# PR9023.net
KiCad netlist of a schematic drawn in EAGLE
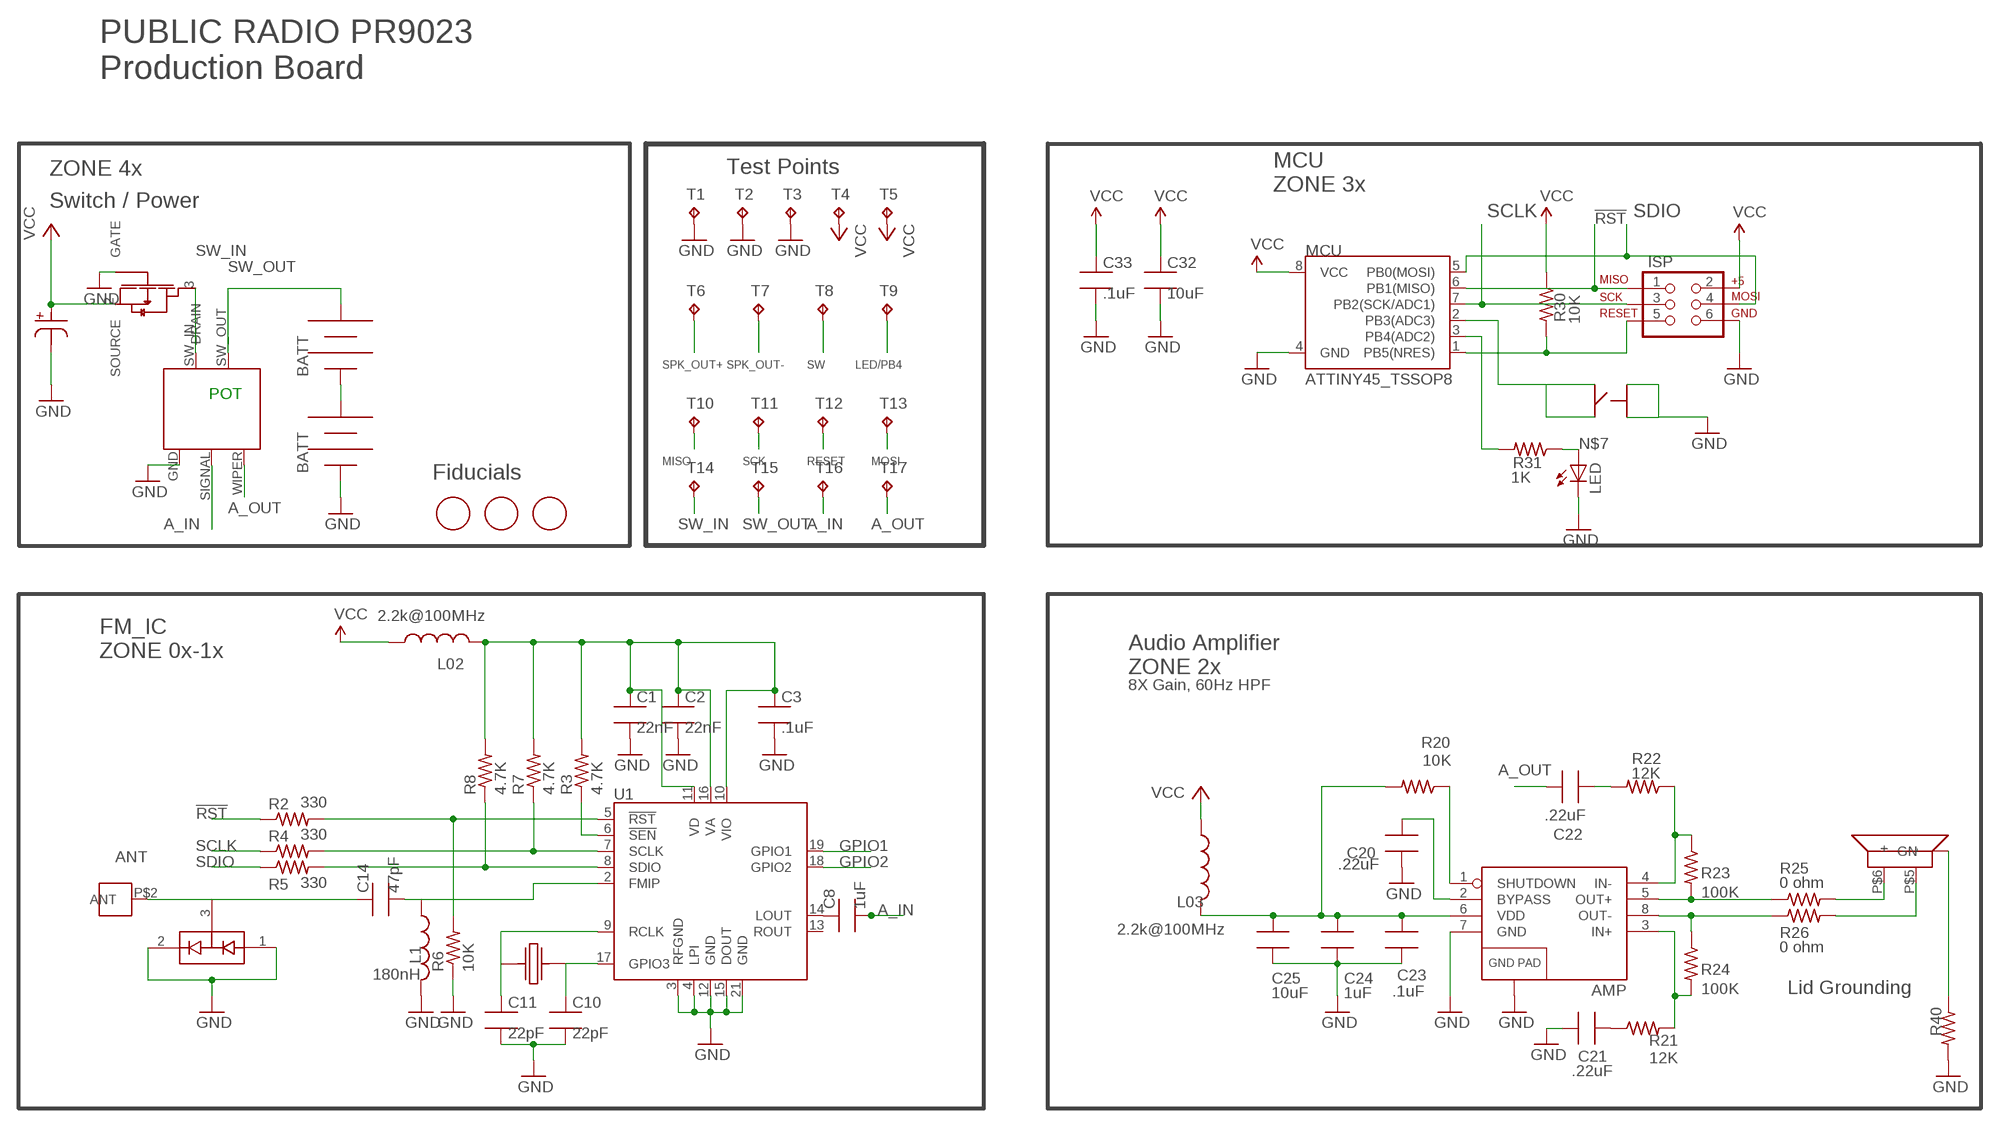
[diagram p0: schematic, sheet 1]

(export (version "E")
  (design (tool "Eeschema 10.0.6"))
  (components
    (comp (ref "AMP")
      (value "TPA6203A1")
      (footprint "eagle-import:8-MSOP")
      (libsource (lib "eagle-import") (part "TPA6203A1"))
    )
    (comp (ref "ANT_MOUNT")
      (value "DNP")
      (footprint "eagle-import:PEM_M3")
      (libsource (lib "eagle-import") (part "M3_PEMNUT"))
    )
    (comp (ref "C1")
      (value "22nF")
      (footprint "eagle-import:0603_CPL")
      (fields
        (field (name "MFG_PN") "CL10B223KB8NNNC")
        (field (name "TOL") "10%")
        (field (name "VOLTAGE") "16V")
      )
      (libsource (lib "eagle-import") (part "C_SMT_0603_CPL"))
    )
    (comp (ref "C2")
      (value "22nF")
      (footprint "eagle-import:0603_CPL")
      (fields
        (field (name "MFG_PN") "CL10B223KB8NNNC")
        (field (name "TOL") "10%")
        (field (name "VOLTAGE") "16V")
      )
      (libsource (lib "eagle-import") (part "C_SMT_0603_CPL"))
    )
    (comp (ref "C3")
      (value ".1uF")
      (footprint "eagle-import:0603_CPL")
      (fields
        (field (name "MFG_PN") "CL10B104KB8SFNC")
        (field (name "TOL") "10%")
        (field (name "VOLTAGE") "16V")
      )
      (libsource (lib "eagle-import") (part "C_SMT_0603_CPL"))
    )
    (comp (ref "C8")
      (value "1uF")
      (footprint "eagle-import:0603_CPL")
      (fields
        (field (name "MFG_PN") "CL10B105KP8NNNC")
        (field (name "TOL") "10%")
        (field (name "VOLTAGE") "10V")
      )
      (libsource (lib "eagle-import") (part "C_SMT_0603_CPL"))
    )
    (comp (ref "C10")
      (value "22pF")
      (footprint "eagle-import:0603_CPL")
      (fields
        (field (name "MFG_PN") "C1608C0G1H220J080AA")
        (field (name "TOL") "5%")
        (field (name "VOLTAGE") "50V")
      )
      (libsource (lib "eagle-import") (part "C_SMT_0603_CPL"))
    )
    (comp (ref "C11")
      (value "22pF")
      (footprint "eagle-import:0603_CPL")
      (fields
        (field (name "MFG_PN") "C1608C0G1H220J080AA")
        (field (name "TOL") "5%")
        (field (name "VOLTAGE") "50V")
      )
      (libsource (lib "eagle-import") (part "C_SMT_0603_CPL"))
    )
    (comp (ref "C14")
      (value "47pF")
      (footprint "eagle-import:0603_CPL")
      (fields
        (field (name "MFG_PN") "CL10C470JB8NCNC")
        (field (name "TOL") "5%")
        (field (name "VOLTAGE") "50V")
      )
      (libsource (lib "eagle-import") (part "C_SMT_0603_CPL"))
    )
    (comp (ref "C20")
      (value ".22uF")
      (footprint "eagle-import:0603_CPL")
      (fields
        (field (name "MFG_PN") "C1608X7R1C224K080AC")
        (field (name "TOL") "10%")
        (field (name "VOLTAGE") "16V")
      )
      (libsource (lib "eagle-import") (part "C_SMT_0603_CPL"))
    )
    (comp (ref "C21")
      (value ".22uF")
      (footprint "eagle-import:0603_CPL")
      (fields
        (field (name "MFG_PN") "C1608X7R1C224K080AC")
        (field (name "TOL") "10%")
        (field (name "VOLTAGE") "16V")
      )
      (libsource (lib "eagle-import") (part "C_SMT_0603_CPL"))
    )
    (comp (ref "C22")
      (value ".22uF")
      (footprint "eagle-import:0603_CPL")
      (fields
        (field (name "MFG_PN") "C1608X7R1C224K080AC")
        (field (name "TOL") "10%")
        (field (name "VOLTAGE") "16V")
      )
      (libsource (lib "eagle-import") (part "C_SMT_0603_CPL"))
    )
    (comp (ref "C23")
      (value ".1uF")
      (footprint "eagle-import:0603_CPL")
      (fields
        (field (name "MFG_PN") "CL10B104KB8SFNC")
        (field (name "TOL") "10%")
        (field (name "VOLTAGE") "16V")
      )
      (libsource (lib "eagle-import") (part "C_SMT_0603_CPL"))
    )
    (comp (ref "C24")
      (value "1uF")
      (footprint "eagle-import:0603_CPL")
      (fields
        (field (name "MFG_PN") "CL10B105KP8NNNC")
        (field (name "TOL") "10%")
        (field (name "VOLTAGE") "10V")
      )
      (libsource (lib "eagle-import") (part "C_SMT_0603_CPL"))
    )
    (comp (ref "C25")
      (value "10uF")
      (footprint "eagle-import:0603_CPL")
      (fields
        (field (name "MFG_PN") "CL10A106MQ8NNNC")
        (field (name "TOL") "20%")
        (field (name "VOLTAGE") "6.3V")
      )
      (libsource (lib "eagle-import") (part "C_SMT_0603_CPL"))
    )
    (comp (ref "C32")
      (value "10uF")
      (footprint "eagle-import:0603_CPL")
      (fields
        (field (name "MFG_PN") "CL10A106MQ8NNNC")
        (field (name "TOL") "20%")
        (field (name "VOLTAGE") "6.3V")
      )
      (libsource (lib "eagle-import") (part "C_SMT_0603_CPL"))
    )
    (comp (ref "C33")
      (value ".1uF")
      (footprint "eagle-import:0603_CPL")
      (fields
        (field (name "MFG_PN") "CL10B104KB8SFNC")
        (field (name "TOL") "10%")
        (field (name "VOLTAGE") "16V")
      )
      (libsource (lib "eagle-import") (part "C_SMT_0603_CPL"))
    )
    (comp (ref "C40")
      (value "220uF")
      (footprint "eagle-import:NICHICON_UD_63")
      (fields (field (name "TOL") "20%") (field (name "VOLTAGE") "16V"))
      (libsource (lib "eagle-import") (part "NICHICON_SERIESUD"))
    )
    (comp (ref "D1")
      (value "BAV99")
      (footprint "eagle-import:SOT23_CPL")
      (fields (field (name "MFG_PN") "BAV99,215"))
      (libsource (lib "eagle-import") (part "BAV99"))
    )
    (comp (ref "FET1")
      (value "AO3435")
      (footprint "eagle-import:SOT23_CPL")
      (fields (field (name "MFG_PN") "AO3435"))
      (libsource (lib "eagle-import") (part "AO3435"))
    )
    (comp (ref "ISP")
      (value "AVR_SPI_PRG_6NS")
      (footprint "eagle-import:2X3-NS")
      (libsource (lib "eagle-import") (part "AVR_SPI_PRG_6NS"))
    )
    (comp (ref "JP5")
      (value "BK-92_MPD_AA_BATT_CLIP")
      (footprint "eagle-import:BK92_AA_BATT")
      (fields (field (name "MFG_PN") "2 of BK92 - supplied by CL Labs"))
      (libsource (lib "eagle-import") (part "BK-92_MPD_AA_BATT_CLIP"))
    )
    (comp (ref "JP6")
      (value "BK-92_MPD_AA_BATT_CLIP")
      (footprint "eagle-import:BK92_AA_BATT")
      (fields (field (name "MFG_PN") "2 of BK92 - supplied by CL Labs"))
      (libsource (lib "eagle-import") (part "BK-92_MPD_AA_BATT_CLIP"))
    )
    (comp (ref "L1")
      (value "180nH")
      (footprint "eagle-import:0805_ADAFRUIT")
      (fields
        (field (name "CURRENT") "400mA")
        (field (name "DCR") "640m")
        (field (name "MFG_PN") "AISC-0805-R18J-T")
        (field (name "TOL") "5%")
      )
      (libsource (lib "eagle-import") (part "L_SMT_0805_ADAFRUIT"))
    )
    (comp (ref "L02")
      (value "2.2k@100MHz")
      (footprint "eagle-import:0603_CPL")
      (fields
        (field (name "CURRENT") "150mA")
        (field (name "DCR") "2.3")
        (field (name "MFG_PN") "HZ0603A222R-10")
      )
      (libsource (lib "eagle-import") (part "L_SMT_0603_CPL"))
    )
    (comp (ref "L03")
      (value "2.2k@100MHz")
      (footprint "eagle-import:0603_CPL")
      (fields
        (field (name "CURRENT") "150mA")
        (field (name "DCR") "2.3")
        (field (name "MFG_PN") "HZ0603A222R-10")
      )
      (libsource (lib "eagle-import") (part "L_SMT_0603_CPL"))
    )
    (comp (ref "LED")
      (value "LEDCHIPLED_0805")
      (footprint "eagle-import:CHIPLED_0805")
      (libsource (lib "eagle-import") (part "LEDCHIPLED_0805"))
    )
    (comp (ref "MARK1")
      (value "FIDUCIAL")
      (footprint "eagle-import:FIDUCIAL_1MM")
      (libsource (lib "eagle-import") (part "FIDUCIAL"))
    )
    (comp (ref "MARK2")
      (value "FIDUCIAL")
      (footprint "eagle-import:FIDUCIAL_1MM")
      (libsource (lib "eagle-import") (part "FIDUCIAL"))
    )
    (comp (ref "MARK3")
      (value "FIDUCIAL")
      (footprint "eagle-import:FIDUCIAL_1MM")
      (libsource (lib "eagle-import") (part "FIDUCIAL"))
    )
    (comp (ref "MCU")
      (value "ATTINY45_TSSOP8")
      (footprint "eagle-import:TSSOP-8")
      (libsource (lib "eagle-import") (part "ATTINY45_TSSOP8"))
    )
    (comp (ref "R1")
      (value "RV170SF_TAIWANA_POT_SW")
      (footprint "eagle-import:RV170SF_SW_POT")
      (fields (field (name "MFG_PN") "RV170SF-43-20F-A10K - supplied by CL Labs"))
      (libsource (lib "eagle-import") (part "RV170SF_TAIWANA_POT_SW"))
    )
    (comp (ref "R2")
      (value "330")
      (footprint "eagle-import:0603_CPL")
      (fields (field (name "MFG_PN") "MCR03ERTJ331") (field (name "POWER") "1/10W") (field (name "TOL") "5%"))
      (libsource (lib "eagle-import") (part "R_SMT_R0603_CPL"))
    )
    (comp (ref "R3")
      (value "4.7K")
      (footprint "eagle-import:0603_CPL")
      (fields
        (field (name "MFG_PN") "ERJ-3EKF4701V")
        (field (name "POWER") "1/10W")
        (field (name "TOL") "1%")
      )
      (libsource (lib "eagle-import") (part "R_SMT_R0603_CPL"))
    )
    (comp (ref "R4")
      (value "330")
      (footprint "eagle-import:0603_CPL")
      (fields (field (name "MFG_PN") "MCR03ERTJ331") (field (name "POWER") "1/10W") (field (name "TOL") "5%"))
      (libsource (lib "eagle-import") (part "R_SMT_R0603_CPL"))
    )
    (comp (ref "R5")
      (value "330")
      (footprint "eagle-import:0603_CPL")
      (fields (field (name "MFG_PN") "MCR03ERTJ331") (field (name "POWER") "1/10W") (field (name "TOL") "5%"))
      (libsource (lib "eagle-import") (part "R_SMT_R0603_CPL"))
    )
    (comp (ref "R6")
      (value "10K")
      (footprint "eagle-import:0603_CPL")
      (fields
        (field (name "MFG_PN") "ERJ-3GEYJ103V")
        (field (name "POWER") "1/10W")
        (field (name "TOL") "5%")
      )
      (libsource (lib "eagle-import") (part "R_SMT_R0603_CPL"))
    )
    (comp (ref "R7")
      (value "4.7K")
      (footprint "eagle-import:0603_CPL")
      (fields
        (field (name "MFG_PN") "ERJ-3EKF4701V")
        (field (name "POWER") "1/10W")
        (field (name "TOL") "1%")
      )
      (libsource (lib "eagle-import") (part "R_SMT_R0603_CPL"))
    )
    (comp (ref "R8")
      (value "4.7K")
      (footprint "eagle-import:0603_CPL")
      (fields
        (field (name "MFG_PN") "ERJ-3EKF4701V")
        (field (name "POWER") "1/10W")
        (field (name "TOL") "1%")
      )
      (libsource (lib "eagle-import") (part "R_SMT_R0603_CPL"))
    )
    (comp (ref "R20")
      (value "10K")
      (footprint "eagle-import:0603_CPL")
      (fields
        (field (name "MFG_PN") "ERJ-3GEYJ103V")
        (field (name "POWER") "1/10W")
        (field (name "TOL") "5%")
      )
      (libsource (lib "eagle-import") (part "R_SMT_R0603_CPL"))
    )
    (comp (ref "R21")
      (value "12K")
      (footprint "eagle-import:0603_CPL")
      (fields
        (field (name "MFG_PN") "RC0603FR-0712KL")
        (field (name "POWER") "1/10W")
        (field (name "TOL") "1%")
      )
      (libsource (lib "eagle-import") (part "R_SMT_R0603_CPL"))
    )
    (comp (ref "R22")
      (value "12K")
      (footprint "eagle-import:0603_CPL")
      (fields
        (field (name "MFG_PN") "RC0603FR-0712KL")
        (field (name "POWER") "1/10W")
        (field (name "TOL") "1%")
      )
      (libsource (lib "eagle-import") (part "R_SMT_R0603_CPL"))
    )
    (comp (ref "R23")
      (value "100K")
      (footprint "eagle-import:0603_CPL")
      (fields
        (field (name "MFG_PN") "ERJ-3EKF1003V")
        (field (name "POWER") "1/10W")
        (field (name "TOL") "1%")
      )
      (libsource (lib "eagle-import") (part "R_SMT_R0603_CPL"))
    )
    (comp (ref "R24")
      (value "100K")
      (footprint "eagle-import:0603_CPL")
      (fields
        (field (name "MFG_PN") "ERJ-3EKF1003V")
        (field (name "POWER") "1/10W")
        (field (name "TOL") "1%")
      )
      (libsource (lib "eagle-import") (part "R_SMT_R0603_CPL"))
    )
    (comp (ref "R25")
      (value "0 ohm")
      (footprint "eagle-import:0805_ADAFRUIT")
      (fields (field (name "MFG_PN") "ERJ-6GEY0R00V "))
      (libsource (lib "eagle-import") (part "R_SMT_0805_ADAFRUIT"))
    )
    (comp (ref "R26")
      (value "0 ohm")
      (footprint "eagle-import:0805_ADAFRUIT")
      (fields (field (name "MFG_PN") "ERJ-6GEY0R00V "))
      (libsource (lib "eagle-import") (part "R_SMT_0805_ADAFRUIT"))
    )
    (comp (ref "R30")
      (value "10K")
      (footprint "eagle-import:0603_CPL")
      (fields
        (field (name "MFG_PN") "ERJ-3GEYJ103V")
        (field (name "POWER") "1/10W")
        (field (name "TOL") "5%")
      )
      (libsource (lib "eagle-import") (part "R_SMT_R0603_CPL"))
    )
    (comp (ref "R31")
      (value "1K")
      (footprint "eagle-import:0603_CPL")
      (fields
        (field (name "MFG_PN") "ERJ-3EKF1001V")
        (field (name "POWER") "1/10W")
        (field (name "TOL") "1%")
      )
      (libsource (lib "eagle-import") (part "R_SMT_R0603_CPL"))
    )
    (comp (ref "R40")
      (value "DNP")
      (footprint "eagle-import:0603_CPL")
      (fields (field (name "MFG_PN") "ERJ-3GEY0R00V"))
      (libsource (lib "eagle-import") (part "R_SMT_R0603_CPL"))
    )
    (comp (ref "SPKR_PLACE")
      (value "DNP")
      (footprint "eagle-import:PR2024_SPKR_PLACE")
      (libsource (lib "eagle-import") (part "PR9024_SPKR"))
    )
    (comp (ref "SW1")
      (value "ESWT_TL3315")
      (footprint "eagle-import:E_SWITCH_TL3315")
      (libsource (lib "eagle-import") (part "ESWT_TL3315"))
    )
    (comp (ref "T1")
      (value "TPTP20R")
      (footprint "eagle-import:TP20R")
      (libsource (lib "eagle-import") (part "TPTP20R"))
    )
    (comp (ref "T2")
      (value "TPTP20R")
      (footprint "eagle-import:TP20R")
      (libsource (lib "eagle-import") (part "TPTP20R"))
    )
    (comp (ref "T3")
      (value "TPTP20R")
      (footprint "eagle-import:TP20R")
      (libsource (lib "eagle-import") (part "TPTP20R"))
    )
    (comp (ref "T4")
      (value "TPTP20R")
      (footprint "eagle-import:TP20R")
      (libsource (lib "eagle-import") (part "TPTP20R"))
    )
    (comp (ref "T5")
      (value "TPTP20R")
      (footprint "eagle-import:TP20R")
      (libsource (lib "eagle-import") (part "TPTP20R"))
    )
    (comp (ref "T6")
      (value "TPTP20R")
      (footprint "eagle-import:TP20R")
      (libsource (lib "eagle-import") (part "TPTP20R"))
    )
    (comp (ref "T7")
      (value "TPTP20R")
      (footprint "eagle-import:TP20R")
      (libsource (lib "eagle-import") (part "TPTP20R"))
    )
    (comp (ref "T8")
      (value "TPTP20R")
      (footprint "eagle-import:TP20R")
      (libsource (lib "eagle-import") (part "TPTP20R"))
    )
    (comp (ref "T9")
      (value "TPTP20R")
      (footprint "eagle-import:TP20R")
      (libsource (lib "eagle-import") (part "TPTP20R"))
    )
    (comp (ref "T10")
      (value "TPTP20R")
      (footprint "eagle-import:TP20R")
      (libsource (lib "eagle-import") (part "TPTP20R"))
    )
    (comp (ref "T11")
      (value "TPTP20R")
      (footprint "eagle-import:TP20R")
      (libsource (lib "eagle-import") (part "TPTP20R"))
    )
    (comp (ref "T12")
      (value "TPTP20R")
      (footprint "eagle-import:TP20R")
      (libsource (lib "eagle-import") (part "TPTP20R"))
    )
    (comp (ref "T13")
      (value "TPTP20R")
      (footprint "eagle-import:TP20R")
      (libsource (lib "eagle-import") (part "TPTP20R"))
    )
    (comp (ref "T14")
      (value "TPTP20R")
      (footprint "eagle-import:TP20R")
      (libsource (lib "eagle-import") (part "TPTP20R"))
    )
    (comp (ref "T15")
      (value "TPTP20R")
      (footprint "eagle-import:TP20R")
      (libsource (lib "eagle-import") (part "TPTP20R"))
    )
    (comp (ref "T16")
      (value "TPTP20R")
      (footprint "eagle-import:TP20R")
      (libsource (lib "eagle-import") (part "TPTP20R"))
    )
    (comp (ref "T17")
      (value "TPTP20R")
      (footprint "eagle-import:TP20R")
      (libsource (lib "eagle-import") (part "TPTP20R"))
    )
    (comp (ref "U1")
      (value "SI4702-C19-GMR")
      (footprint "eagle-import:SI470X_20_QFN")
      (fields (field (name "MFG_PN") "Si4702 C19 GM - supplied by CL Labs"))
      (libsource (lib "eagle-import") (part "SI4702-C19-GMR"))
    )
    (comp (ref "X1")
      (value "ABS25XTAL")
      (footprint "eagle-import:4-SOJ")
      (libsource (lib "eagle-import") (part "ABS25XTAL"))
    )
  )
  (nets
    (net (code "1") (name "/ANT") (class "Default")
      (node (ref "ANT_MOUNT") (pin "P$2") (pinfunction "ANT_P$2") (pintype "bidirectional"))
      (node (ref "C14") (pin "1") (pinfunction "1_1") (pintype "passive"))
      (node (ref "D1") (pin "3") (pinfunction "COM_3") (pintype "bidirectional"))
    )
    (net (code "2") (name "/A_IN") (class "Default")
      (node (ref "C8") (pin "2") (pinfunction "2_2") (pintype "passive"))
      (node (ref "R1") (pin "SIGNAL") (pinfunction "SIGNAL_SIGNAL") (pintype "bidirectional"))
      (node (ref "T16") (pin "TP") (pinfunction "TP_TP") (pintype "input"))
    )
    (net (code "3") (name "/A_OUT") (class "Default")
      (node (ref "C22") (pin "2") (pinfunction "2_2") (pintype "passive"))
      (node (ref "R1") (pin "WIPER") (pinfunction "WIPER_WIPER") (pintype "bidirectional"))
      (node (ref "T17") (pin "TP") (pinfunction "TP_TP") (pintype "input"))
    )
    (net (code "4") (name "/GPIO1") (class "Default")
      (node (ref "U1") (pin "19") (pinfunction "GPIO1_19") (pintype "bidirectional"))
    )
    (net (code "5") (name "/GPIO2") (class "Default")
      (node (ref "U1") (pin "18") (pinfunction "GPIO2_18") (pintype "bidirectional"))
    )
    (net (code "6") (name "/LED{slash}PB4") (class "Default")
      (node (ref "MCU") (pin "3") (pinfunction "PB4(ADC2)_3") (pintype "bidirectional"))
      (node (ref "R31") (pin "2") (pinfunction "2_2") (pintype "passive"))
      (node (ref "T9") (pin "TP") (pinfunction "TP_TP") (pintype "input"))
    )
    (net (code "7") (name "/N$7") (class "Default")
      (node (ref "LED") (pin "A") (pinfunction "A_A") (pintype "passive"))
      (node (ref "R31") (pin "1") (pinfunction "1_1") (pintype "passive"))
    )
    (net (code "8") (name "/RESET") (class "Default")
      (node (ref "ISP") (pin "5") (pinfunction "5_5") (pintype "passive"))
      (node (ref "MCU") (pin "1") (pinfunction "PB5(NRES)_1") (pintype "bidirectional"))
      (node (ref "R30") (pin "2") (pinfunction "2_2") (pintype "passive"))
      (node (ref "T12") (pin "TP") (pinfunction "TP_TP") (pintype "input"))
    )
    (net (code "9") (name "/SCLK") (class "Default")
      (node (ref "ISP") (pin "3") (pinfunction "3_3") (pintype "passive"))
      (node (ref "MCU") (pin "7") (pinfunction "PB2(SCK/ADC1)_7") (pintype "bidirectional"))
      (node (ref "R4") (pin "1") (pinfunction "1_1") (pintype "passive"))
      (node (ref "T11") (pin "TP") (pinfunction "TP_TP") (pintype "input"))
    )
    (net (code "10") (name "/SDIO") (class "Default")
      (node (ref "ISP") (pin "4") (pinfunction "4_4") (pintype "passive"))
      (node (ref "MCU") (pin "5") (pinfunction "PB0(MOSI)_5") (pintype "bidirectional"))
      (node (ref "R5") (pin "1") (pinfunction "1_1") (pintype "passive"))
      (node (ref "T13") (pin "TP") (pinfunction "TP_TP") (pintype "input"))
    )
    (net (code "11") (name "/SPK_OUT+") (class "Default")
      (node (ref "R25") (pin "2") (pinfunction "2_2") (pintype "passive"))
      (node (ref "SPKR_PLACE") (pin "P$6") (pinfunction "+_P$6") (pintype "bidirectional"))
      (node (ref "T6") (pin "TP") (pinfunction "TP_TP") (pintype "input"))
    )
    (net (code "12") (name "/SPK_OUT-") (class "Default")
      (node (ref "R26") (pin "2") (pinfunction "2_2") (pintype "passive"))
      (node (ref "SPKR_PLACE") (pin "P$5") (pinfunction "-_P$5") (pintype "bidirectional"))
      (node (ref "T7") (pin "TP") (pinfunction "TP_TP") (pintype "input"))
    )
    (net (code "13") (name "/SW") (class "Default")
      (node (ref "MCU") (pin "2") (pinfunction "PB3(ADC3)_2") (pintype "bidirectional"))
      (node (ref "SW1") (pin "P$3") (pinfunction "P$3_P$3") (pintype "bidirectional"))
      (node (ref "SW1") (pin "P$4") (pinfunction "P$4_P$4") (pintype "bidirectional"))
      (node (ref "T8") (pin "TP") (pinfunction "TP_TP") (pintype "input"))
    )
    (net (code "14") (name "/SW_IN") (class "Default")
      (node (ref "FET1") (pin "3") (pinfunction "DRAIN_3") (pintype "bidirectional"))
      (node (ref "R1") (pin "SW_IN") (pinfunction "SW_IN_SW_IN") (pintype "bidirectional"))
      (node (ref "T14") (pin "TP") (pinfunction "TP_TP") (pintype "input"))
    )
    (net (code "15") (name "/SW_OUT") (class "Default")
      (node (ref "JP5") (pin "POS") (pinfunction "POS_POS") (pintype "bidirectional"))
      (node (ref "JP5") (pin "POS@2") (pinfunction "POS_POS@2") (pintype "bidirectional"))
      (node (ref "R1") (pin "SW_OUT") (pinfunction "SW_OUT_SW_OUT") (pintype "bidirectional"))
      (node (ref "T15") (pin "TP") (pinfunction "TP_TP") (pintype "input"))
    )
    (net (code "16") (name "/~{RST}") (class "Default")
      (node (ref "ISP") (pin "1") (pinfunction "1_1") (pintype "passive"))
      (node (ref "MCU") (pin "6") (pinfunction "PB1(MISO)_6") (pintype "bidirectional"))
      (node (ref "R2") (pin "1") (pinfunction "1_1") (pintype "passive"))
      (node (ref "T10") (pin "TP") (pinfunction "TP_TP") (pintype "input"))
    )
    (net (code "17") (name "GND") (class "Default")
      (node (ref "AMP") (pin "7") (pinfunction "GND_7") (pintype "power_in"))
      (node (ref "AMP") (pin "9") (pinfunction "GND_9") (pintype "power_in"))
      (node (ref "C1") (pin "2") (pinfunction "2_2") (pintype "passive"))
      (node (ref "C10") (pin "2") (pinfunction "2_2") (pintype "passive"))
      (node (ref "C11") (pin "2") (pinfunction "2_2") (pintype "passive"))
      (node (ref "C2") (pin "2") (pinfunction "2_2") (pintype "passive"))
      (node (ref "C20") (pin "1") (pinfunction "1_1") (pintype "passive"))
      (node (ref "C21") (pin "1") (pinfunction "1_1") (pintype "passive"))
      (node (ref "C23") (pin "2") (pinfunction "2_2") (pintype "passive"))
      (node (ref "C24") (pin "2") (pinfunction "2_2") (pintype "passive"))
      (node (ref "C25") (pin "2") (pinfunction "2_2") (pintype "passive"))
      (node (ref "C3") (pin "2") (pinfunction "2_2") (pintype "passive"))
      (node (ref "C32") (pin "2") (pinfunction "2_2") (pintype "passive"))
      (node (ref "C33") (pin "2") (pinfunction "2_2") (pintype "passive"))
      (node (ref "C40") (pin "P$2") (pinfunction "P$2_P$2") (pintype "bidirectional"))
      (node (ref "D1") (pin "1") (pinfunction "A1_1") (pintype "bidirectional"))
      (node (ref "D1") (pin "2") (pinfunction "C2_2") (pintype "bidirectional"))
      (node (ref "FET1") (pin "1") (pinfunction "GATE_1") (pintype "bidirectional"))
      (node (ref "ISP") (pin "6") (pinfunction "6_6") (pintype "passive"))
      (node (ref "JP6") (pin "NEG") (pinfunction "NEG_NEG") (pintype "bidirectional"))
      (node (ref "JP6") (pin "NEG@2") (pinfunction "NEG_NEG@2") (pintype "bidirectional"))
      (node (ref "L1") (pin "2") (pinfunction "2_2") (pintype "passive"))
      (node (ref "LED") (pin "C") (pinfunction "C_C") (pintype "passive"))
      (node (ref "MCU") (pin "4") (pinfunction "GND_4") (pintype "bidirectional"))
      (node (ref "R1") (pin "GND") (pinfunction "GND_GND") (pintype "bidirectional"))
      (node (ref "R40") (pin "2") (pinfunction "2_2") (pintype "passive"))
      (node (ref "R6") (pin "1") (pinfunction "1_1") (pintype "passive"))
      (node (ref "SW1") (pin "P$1") (pinfunction "P$1_P$1") (pintype "bidirectional"))
      (node (ref "SW1") (pin "P$2") (pinfunction "P$2_P$2") (pintype "bidirectional"))
      (node (ref "T1") (pin "TP") (pinfunction "TP_TP") (pintype "input"))
      (node (ref "T2") (pin "TP") (pinfunction "TP_TP") (pintype "input"))
      (node (ref "T3") (pin "TP") (pinfunction "TP_TP") (pintype "input"))
      (node (ref "U1") (pin "12") (pinfunction "GND_12") (pintype "bidirectional"))
      (node (ref "U1") (pin "15") (pinfunction "DOUT_15") (pintype "bidirectional"))
      (node (ref "U1") (pin "21") (pinfunction "GND_21") (pintype "bidirectional"))
      (node (ref "U1") (pin "3") (pinfunction "RFGND_3") (pintype "bidirectional"))
      (node (ref "U1") (pin "4") (pinfunction "LPI_4") (pintype "bidirectional"))
    )
    (net (code "18") (name "Net-(AMP-BYPASS)") (class "Default")
      (node (ref "AMP") (pin "2") (pinfunction "BYPASS_2") (pintype "bidirectional"))
      (node (ref "C20") (pin "2") (pinfunction "2_2") (pintype "passive"))
    )
    (net (code "19") (name "Net-(AMP-IN+)") (class "Default")
      (node (ref "AMP") (pin "3") (pinfunction "IN+_3") (pintype "bidirectional"))
      (node (ref "R21") (pin "2") (pinfunction "2_2") (pintype "passive"))
      (node (ref "R24") (pin "2") (pinfunction "2_2") (pintype "passive"))
    )
    (net (code "20") (name "Net-(AMP-IN-)") (class "Default")
      (node (ref "AMP") (pin "4") (pinfunction "IN-_4") (pintype "bidirectional"))
      (node (ref "R22") (pin "1") (pinfunction "1_1") (pintype "passive"))
      (node (ref "R23") (pin "1") (pinfunction "1_1") (pintype "passive"))
    )
    (net (code "21") (name "Net-(AMP-OUT+)") (class "Default")
      (node (ref "AMP") (pin "5") (pinfunction "OUT+_5") (pintype "bidirectional"))
      (node (ref "R23") (pin "2") (pinfunction "2_2") (pintype "passive"))
      (node (ref "R25") (pin "1") (pinfunction "1_1") (pintype "passive"))
    )
    (net (code "22") (name "Net-(AMP-OUT-)") (class "Default")
      (node (ref "AMP") (pin "8") (pinfunction "OUT-_8") (pintype "bidirectional"))
      (node (ref "R24") (pin "1") (pinfunction "1_1") (pintype "passive"))
      (node (ref "R26") (pin "1") (pinfunction "1_1") (pintype "passive"))
    )
    (net (code "23") (name "Net-(AMP-SHUTDOWN)") (class "Default")
      (node (ref "AMP") (pin "1") (pinfunction "SHUTDOWN_1") (pintype "input"))
      (node (ref "R20") (pin "1") (pinfunction "1_1") (pintype "passive"))
    )
    (net (code "24") (name "Net-(AMP-VDD)") (class "Default")
      (node (ref "AMP") (pin "6") (pinfunction "VDD_6") (pintype "power_in"))
      (node (ref "C23") (pin "1") (pinfunction "1_1") (pintype "passive"))
      (node (ref "C24") (pin "1") (pinfunction "1_1") (pintype "passive"))
      (node (ref "C25") (pin "1") (pinfunction "1_1") (pintype "passive"))
      (node (ref "L03") (pin "2") (pinfunction "2_2") (pintype "passive"))
      (node (ref "R20") (pin "2") (pinfunction "2_2") (pintype "passive"))
    )
    (net (code "25") (name "Net-(C21-Pad2)") (class "Default")
      (node (ref "C21") (pin "2") (pinfunction "2_2") (pintype "passive"))
      (node (ref "R21") (pin "1") (pinfunction "1_1") (pintype "passive"))
    )
    (net (code "26") (name "Net-(C22-Pad1)") (class "Default")
      (node (ref "C22") (pin "1") (pinfunction "1_1") (pintype "passive"))
      (node (ref "R22") (pin "2") (pinfunction "2_2") (pintype "passive"))
    )
    (net (code "27") (name "Net-(JP5-NEG-PadNEG@2)") (class "Default")
      (node (ref "JP5") (pin "NEG") (pinfunction "NEG_NEG") (pintype "bidirectional"))
      (node (ref "JP5") (pin "NEG@2") (pinfunction "NEG_NEG@2") (pintype "bidirectional"))
      (node (ref "JP6") (pin "POS") (pinfunction "POS_POS") (pintype "bidirectional"))
      (node (ref "JP6") (pin "POS@2") (pinfunction "POS_POS@2") (pintype "bidirectional"))
    )
    (net (code "28") (name "Net-(SPKR_PLACE-GN)") (class "Default")
      (node (ref "R40") (pin "1") (pinfunction "1_1") (pintype "passive"))
      (node (ref "SPKR_PLACE") (pin "P$4") (pinfunction "GN_P$4") (pintype "bidirectional"))
    )
    (net (code "29") (name "Net-(U1-FMIP)") (class "Default")
      (node (ref "C14") (pin "2") (pinfunction "2_2") (pintype "passive"))
      (node (ref "L1") (pin "1") (pinfunction "1_1") (pintype "passive"))
      (node (ref "U1") (pin "2") (pinfunction "FMIP_2") (pintype "bidirectional"))
    )
    (net (code "30") (name "Net-(U1-GPIO3)") (class "Default")
      (node (ref "C10") (pin "1") (pinfunction "1_1") (pintype "passive"))
      (node (ref "U1") (pin "17") (pinfunction "GPIO3_17") (pintype "bidirectional"))
      (node (ref "X1") (pin "P$4") (pinfunction "P$4_P$4") (pintype "bidirectional"))
    )
    (net (code "31") (name "Net-(U1-LOUT)") (class "Default")
      (node (ref "C8") (pin "1") (pinfunction "1_1") (pintype "passive"))
      (node (ref "U1") (pin "14") (pinfunction "LOUT_14") (pintype "bidirectional"))
    )
    (net (code "32") (name "Net-(U1-RCLK)") (class "Default")
      (node (ref "C11") (pin "1") (pinfunction "1_1") (pintype "passive"))
      (node (ref "U1") (pin "9") (pinfunction "RCLK_9") (pintype "bidirectional"))
      (node (ref "X1") (pin "P$1") (pinfunction "P$1_P$1") (pintype "bidirectional"))
    )
    (net (code "33") (name "Net-(U1-SCLK)") (class "Default")
      (node (ref "R4") (pin "2") (pinfunction "2_2") (pintype "passive"))
      (node (ref "R7") (pin "1") (pinfunction "1_1") (pintype "passive"))
      (node (ref "U1") (pin "7") (pinfunction "SCLK_7") (pintype "bidirectional"))
    )
    (net (code "34") (name "Net-(U1-SDIO)") (class "Default")
      (node (ref "R5") (pin "2") (pinfunction "2_2") (pintype "passive"))
      (node (ref "R8") (pin "1") (pinfunction "1_1") (pintype "passive"))
      (node (ref "U1") (pin "8") (pinfunction "SDIO_8") (pintype "bidirectional"))
    )
    (net (code "35") (name "Net-(U1-VA)") (class "Default")
      (node (ref "C1") (pin "1") (pinfunction "1_1") (pintype "passive"))
      (node (ref "C2") (pin "1") (pinfunction "1_1") (pintype "passive"))
      (node (ref "C3") (pin "1") (pinfunction "1_1") (pintype "passive"))
      (node (ref "L02") (pin "2") (pinfunction "2_2") (pintype "passive"))
      (node (ref "R3") (pin "2") (pinfunction "2_2") (pintype "passive"))
      (node (ref "R7") (pin "2") (pinfunction "2_2") (pintype "passive"))
      (node (ref "R8") (pin "2") (pinfunction "2_2") (pintype "passive"))
      (node (ref "U1") (pin "10") (pinfunction "VIO_10") (pintype "bidirectional"))
      (node (ref "U1") (pin "11") (pinfunction "VD_11") (pintype "bidirectional"))
      (node (ref "U1") (pin "16") (pinfunction "VA_16") (pintype "bidirectional"))
    )
    (net (code "36") (name "Net-(U1-~{RST})") (class "Default")
      (node (ref "R2") (pin "2") (pinfunction "2_2") (pintype "passive"))
      (node (ref "R6") (pin "2") (pinfunction "2_2") (pintype "passive"))
      (node (ref "U1") (pin "5") (pinfunction "~{RST}_5") (pintype "bidirectional"))
    )
    (net (code "37") (name "Net-(U1-~{SEN})") (class "Default")
      (node (ref "R3") (pin "1") (pinfunction "1_1") (pintype "passive"))
      (node (ref "U1") (pin "6") (pinfunction "~{SEN}_6") (pintype "bidirectional"))
    )
    (net (code "38") (name "VCC") (class "Default")
      (node (ref "C32") (pin "1") (pinfunction "1_1") (pintype "passive"))
      (node (ref "C33") (pin "1") (pinfunction "1_1") (pintype "passive"))
      (node (ref "C40") (pin "P$1") (pinfunction "P$1_P$1") (pintype "bidirectional"))
      (node (ref "FET1") (pin "2") (pinfunction "SOURCE_2") (pintype "bidirectional"))
      (node (ref "ISP") (pin "2") (pinfunction "2_2") (pintype "passive"))
      (node (ref "L02") (pin "1") (pinfunction "1_1") (pintype "passive"))
      (node (ref "L03") (pin "1") (pinfunction "1_1") (pintype "passive"))
      (node (ref "MCU") (pin "8") (pinfunction "VCC_8") (pintype "bidirectional"))
      (node (ref "R30") (pin "1") (pinfunction "1_1") (pintype "passive"))
      (node (ref "T4") (pin "TP") (pinfunction "TP_TP") (pintype "input"))
      (node (ref "T5") (pin "TP") (pinfunction "TP_TP") (pintype "input"))
    )
    (net (code "39") (name "unconnected-(U1-ROUT-Pad13)") (class "Default")
      (node (ref "U1") (pin "13") (pinfunction "ROUT_13") (pintype "bidirectional"))
    )
  )
)
